# Reference.net
KiCad netlist of a schematic drawn in Altium Designer
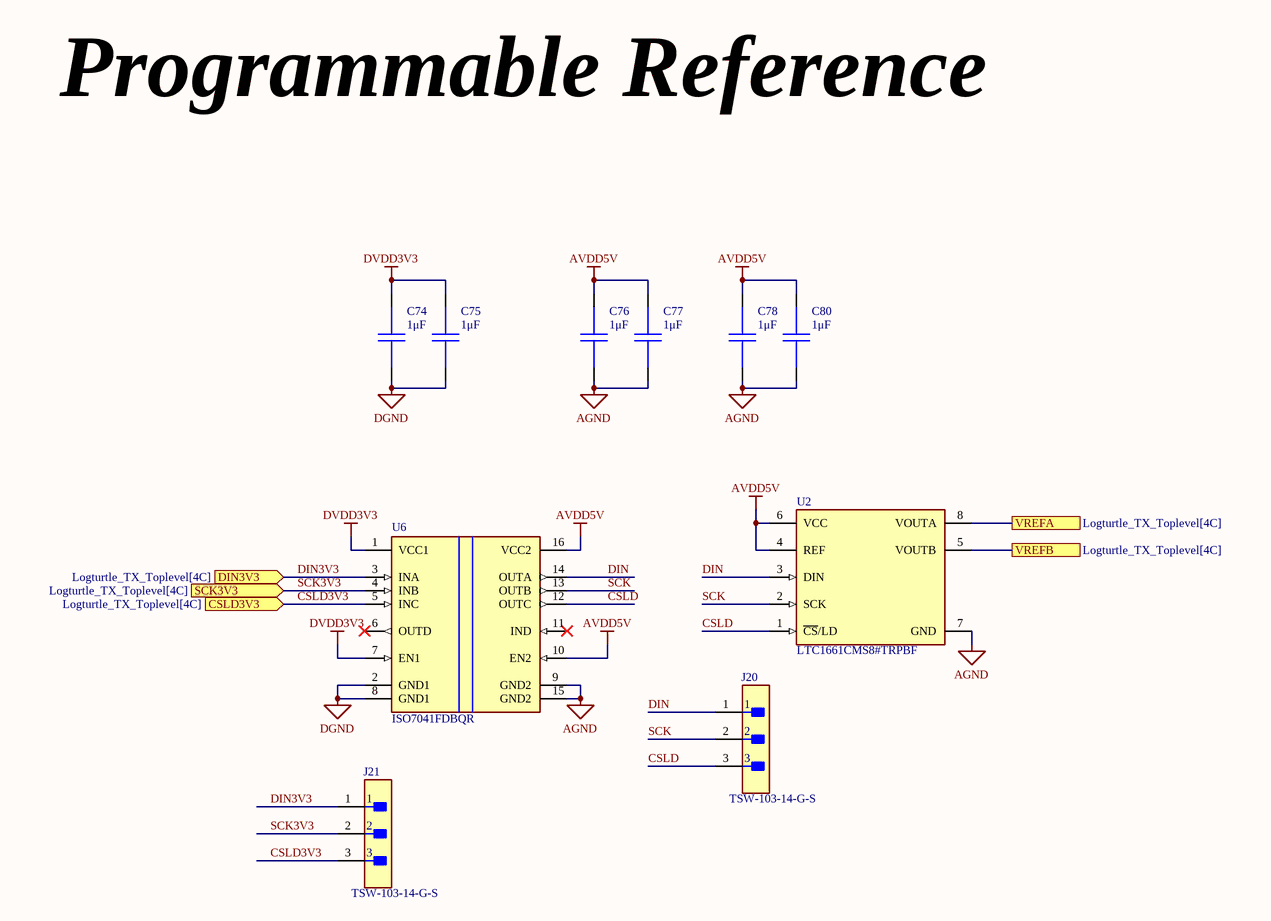
[diagram p0: Reference.SchDoc]

(export (version "E")
  (design (tool "Eeschema 10.0.6"))
  (components
    (comp (ref "C74")
      (value "1μF")
      (footprint "CAPC1608X09N")
      (fields
        (field (name "MANUFACTURER") "Yageo")
        (field (name "MANUFACTURER PART NUMBER") "CC0603KRX7R7BB105")
      )
      (libsource (lib "LOGTURTLE_APR_25_TX") (part "CC0603KRX7R7BB105"))
    )
    (comp (ref "C75")
      (value "1μF")
      (footprint "CAPC1608X09N")
      (fields
        (field (name "MANUFACTURER") "Yageo")
        (field (name "MANUFACTURER PART NUMBER") "CC0603KRX7R7BB105")
      )
      (libsource (lib "LOGTURTLE_APR_25_TX") (part "CC0603KRX7R7BB105"))
    )
    (comp (ref "C76")
      (value "1μF")
      (footprint "CAPC1608X09N")
      (fields
        (field (name "MANUFACTURER") "Yageo")
        (field (name "MANUFACTURER PART NUMBER") "CC0603KRX7R7BB105")
      )
      (libsource (lib "LOGTURTLE_APR_25_TX") (part "CC0603KRX7R7BB105"))
    )
    (comp (ref "C77")
      (value "1μF")
      (footprint "CAPC1608X09N")
      (fields
        (field (name "MANUFACTURER") "Yageo")
        (field (name "MANUFACTURER PART NUMBER") "CC0603KRX7R7BB105")
      )
      (libsource (lib "LOGTURTLE_APR_25_TX") (part "CC0603KRX7R7BB105"))
    )
    (comp (ref "C78")
      (value "1μF")
      (footprint "CAPC1608X09N")
      (fields
        (field (name "MANUFACTURER") "Yageo")
        (field (name "MANUFACTURER PART NUMBER") "CC0603KRX7R7BB105")
      )
      (libsource (lib "LOGTURTLE_APR_25_TX") (part "CC0603KRX7R7BB105"))
    )
    (comp (ref "C80")
      (value "1μF")
      (footprint "CAPC1608X09N")
      (fields
        (field (name "MANUFACTURER") "Yageo")
        (field (name "MANUFACTURER PART NUMBER") "CC0603KRX7R7BB105")
      )
      (libsource (lib "LOGTURTLE_APR_25_TX") (part "CC0603KRX7R7BB105"))
    )
    (comp (ref "J20")
      (value "TSW-103-14-G-S")
      (footprint "FP-TSW-103-14-G-S-MFG")
      (description "CONN HEADER VERT 3POS 2.54MM")
      (libsource (lib "Altium Content Vault") (part "cd3439d6ef35ae5d9b27ec4fdd3e828"))
    )
    (comp (ref "J21")
      (value "TSW-103-14-G-S")
      (footprint "FP-TSW-103-14-G-S-MFG")
      (description "CONN HEADER VERT 3POS 2.54MM")
      (libsource (lib "Altium Content Vault") (part "cd3439d6ef35ae5d9b27ec4fdd3e828"))
    )
    (comp (ref "U2")
      (value "LTC1661CMS8#TRPBF")
      (footprint "FP-MS8-8-05-08-1660-IPC_B")
      (description "IC DAC 10BIT V-OUT 8MSOP")
      (libsource (lib "Altium Content Vault") (part "8511d3b2aeb172de0f69a47bbcb4a97"))
    )
    (comp (ref "U6")
      (value "ISO7041FDBQR")
      (footprint "FP-DBQ0016A-MFG")
      (description "DGTL ISO 3000VRMS 4CH GP 16SSOP")
      (libsource (lib "Altium Content Vault") (part "80109f1b75594fd8fa43878f171b697"))
    )
  )
  (nets
    (net (code "1") (name "/CSLD") (class "Default")
      (node (ref "J20") (pin "3") (pinfunction "3_3") (pintype "passive"))
      (node (ref "U2") (pin "1") (pinfunction "~{CS}/LD_1") (pintype "input"))
      (node (ref "U6") (pin "12") (pinfunction "OUTC_12") (pintype "output"))
    )
    (net (code "2") (name "/CSLD3V3") (class "Default")
      (node (ref "J21") (pin "3") (pinfunction "3_3") (pintype "passive"))
      (node (ref "U6") (pin "5") (pinfunction "INC_5") (pintype "input"))
    )
    (net (code "3") (name "/DIN") (class "Default")
      (node (ref "J20") (pin "1") (pinfunction "1_1") (pintype "passive"))
      (node (ref "U2") (pin "3") (pinfunction "DIN_3") (pintype "input"))
      (node (ref "U6") (pin "14") (pinfunction "OUTA_14") (pintype "output"))
    )
    (net (code "4") (name "/DIN3V3") (class "Default")
      (node (ref "J21") (pin "1") (pinfunction "1_1") (pintype "passive"))
      (node (ref "U6") (pin "3") (pinfunction "INA_3") (pintype "input"))
    )
    (net (code "5") (name "/SCK") (class "Default")
      (node (ref "J20") (pin "2") (pinfunction "2_2") (pintype "passive"))
      (node (ref "U2") (pin "2") (pinfunction "SCK_2") (pintype "input"))
      (node (ref "U6") (pin "13") (pinfunction "OUTB_13") (pintype "output"))
    )
    (net (code "6") (name "/SCK3V3") (class "Default")
      (node (ref "J21") (pin "2") (pinfunction "2_2") (pintype "passive"))
      (node (ref "U6") (pin "4") (pinfunction "INB_4") (pintype "input"))
    )
    (net (code "7") (name "/VREFA") (class "Default")
      (node (ref "U2") (pin "8") (pinfunction "VOUTA_8") (pintype "power_in"))
    )
    (net (code "8") (name "/VREFB") (class "Default")
      (node (ref "U2") (pin "5") (pinfunction "VOUTB_5") (pintype "power_in"))
    )
    (net (code "9") (name "AGND") (class "Default")
      (node (ref "C76") (pin "1") (pinfunction "1_1") (pintype "passive"))
      (node (ref "C77") (pin "1") (pinfunction "1_1") (pintype "passive"))
      (node (ref "C78") (pin "1") (pinfunction "1_1") (pintype "passive"))
      (node (ref "C80") (pin "1") (pinfunction "1_1") (pintype "passive"))
      (node (ref "U2") (pin "7") (pinfunction "GND_7") (pintype "power_in"))
      (node (ref "U6") (pin "15") (pinfunction "GND2_15") (pintype "power_in"))
      (node (ref "U6") (pin "9") (pinfunction "GND2_9") (pintype "power_in"))
    )
    (net (code "10") (name "AVDD5V") (class "Default")
      (node (ref "C76") (pin "2") (pinfunction "2_2") (pintype "passive"))
      (node (ref "C77") (pin "2") (pinfunction "2_2") (pintype "passive"))
      (node (ref "C78") (pin "2") (pinfunction "2_2") (pintype "passive"))
      (node (ref "C80") (pin "2") (pinfunction "2_2") (pintype "passive"))
      (node (ref "U2") (pin "4") (pinfunction "REF_4") (pintype "passive"))
      (node (ref "U2") (pin "6") (pinfunction "VCC_6") (pintype "power_in"))
      (node (ref "U6") (pin "10") (pinfunction "EN2_10") (pintype "input"))
      (node (ref "U6") (pin "16") (pinfunction "VCC2_16") (pintype "power_in"))
    )
    (net (code "11") (name "DGND") (class "Default")
      (node (ref "C74") (pin "1") (pinfunction "1_1") (pintype "passive"))
      (node (ref "C75") (pin "1") (pinfunction "1_1") (pintype "passive"))
      (node (ref "U6") (pin "2") (pinfunction "GND1_2") (pintype "power_in"))
      (node (ref "U6") (pin "8") (pinfunction "GND1_8") (pintype "power_in"))
    )
    (net (code "12") (name "DVDD3V3") (class "Default")
      (node (ref "C74") (pin "2") (pinfunction "2_2") (pintype "passive"))
      (node (ref "C75") (pin "2") (pinfunction "2_2") (pintype "passive"))
      (node (ref "U6") (pin "1") (pinfunction "VCC1_1") (pintype "power_in"))
      (node (ref "U6") (pin "7") (pinfunction "EN1_7") (pintype "input"))
    )
    (net (code "13") (name "unconnected-(U6-IND-Pad11)") (class "Default")
      (node (ref "U6") (pin "11") (pinfunction "IND_11") (pintype "input+no_connect"))
    )
    (net (code "14") (name "unconnected-(U6-OUTD-Pad6)") (class "Default")
      (node (ref "U6") (pin "6") (pinfunction "OUTD_6") (pintype "output+no_connect"))
    )
  )
)
